# motortreiber.net
KiCad netlist of a schematic drawn in EAGLE
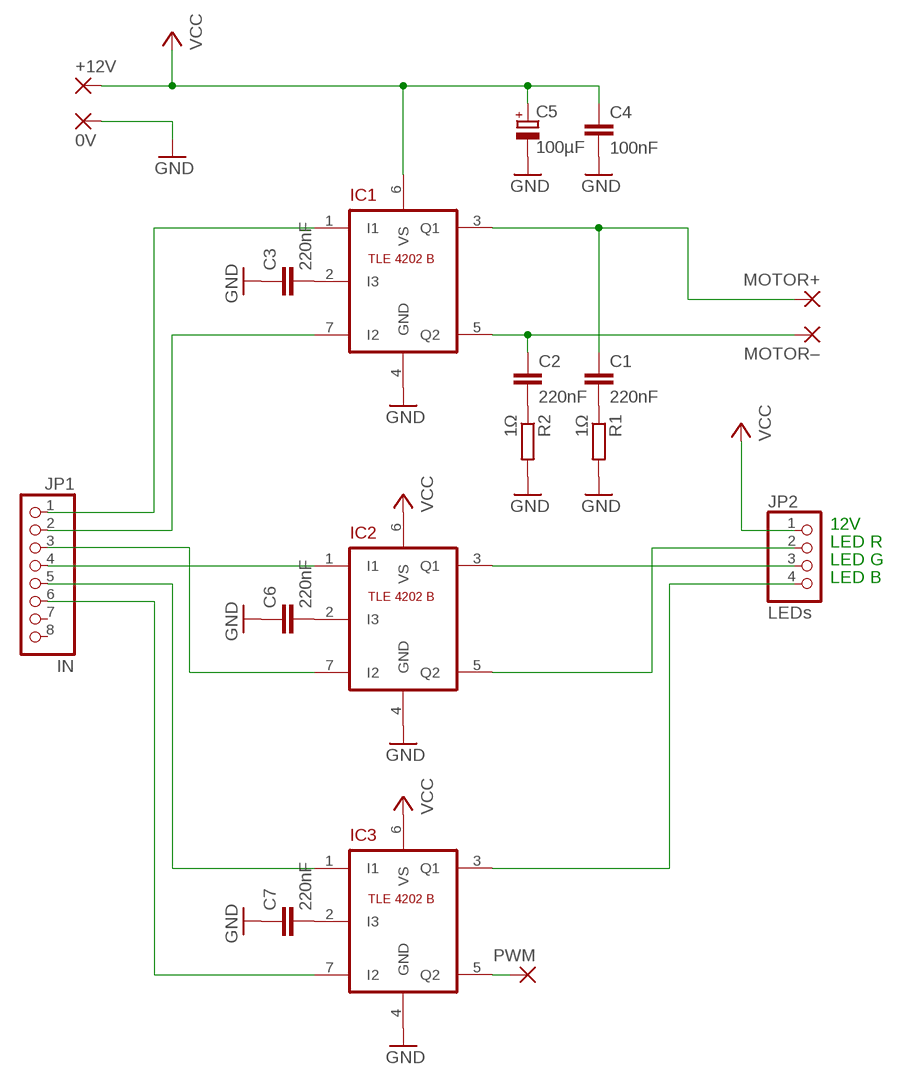
[diagram p0: schematic, sheet 1]

(export (version "E")
  (design (tool "Eeschema 10.0.6"))
  (components
    (comp (ref "+12V")
      (value "WIREPAD2,15/1,0")
      (footprint "eagle-import:2,15_1,0")
      (libsource (lib "eagle-import") (part "WIREPAD2,15/1,0"))
    )
    (comp (ref "0V")
      (value "WIREPAD2,15/1,0")
      (footprint "eagle-import:2,15_1,0")
      (libsource (lib "eagle-import") (part "WIREPAD2,15/1,0"))
    )
    (comp (ref "C1")
      (value "220nF")
      (footprint "eagle-import:C5B2.5")
      (libsource (lib "eagle-import") (part "C5/2.5"))
    )
    (comp (ref "C2")
      (value "220nF")
      (footprint "eagle-import:C5B2.5")
      (libsource (lib "eagle-import") (part "C5/2.5"))
    )
    (comp (ref "C3")
      (value "220nF")
      (footprint "eagle-import:C5B2.5")
      (libsource (lib "eagle-import") (part "C5/2.5"))
    )
    (comp (ref "C4")
      (value "100nF")
      (footprint "eagle-import:C2.5-3")
      (libsource (lib "eagle-import") (part "C2,5-3"))
    )
    (comp (ref "C5")
      (value "100µF")
      (footprint "eagle-import:E2,5-5")
      (libsource (lib "eagle-import") (part "CPOL-EUE2.5-5"))
    )
    (comp (ref "C6")
      (value "220nF")
      (footprint "eagle-import:C5B2.5")
      (libsource (lib "eagle-import") (part "C5/2.5"))
    )
    (comp (ref "C7")
      (value "220nF")
      (footprint "eagle-import:C5B2.5")
      (libsource (lib "eagle-import") (part "C5/2.5"))
    )
    (comp (ref "IC1")
      (value "TLE-4202-B-100MIL")
      (footprint "eagle-import:TO-220-7-BREADBOARD")
      (libsource (lib "eagle-import") (part "TLE-4202-B-100MIL"))
    )
    (comp (ref "IC2")
      (value "TLE-4202-B-100MIL")
      (footprint "eagle-import:TO-220-7-BREADBOARD")
      (libsource (lib "eagle-import") (part "TLE-4202-B-100MIL"))
    )
    (comp (ref "IC3")
      (value "TLE-4202-B-100MIL")
      (footprint "eagle-import:TO-220-7-BREADBOARD")
      (libsource (lib "eagle-import") (part "TLE-4202-B-100MIL"))
    )
    (comp (ref "JP1")
      (value "IN")
      (footprint "eagle-import:1X08")
      (libsource (lib "eagle-import") (part "PINHD-1X8"))
    )
    (comp (ref "JP2")
      (value "LEDs")
      (footprint "eagle-import:1X04")
      (libsource (lib "eagle-import") (part "PINHD-1X4"))
    )
    (comp (ref "MOTOR+")
      (value "WIREPAD2,15/1,0")
      (footprint "eagle-import:2,15_1,0")
      (libsource (lib "eagle-import") (part "WIREPAD2,15/1,0"))
    )
    (comp (ref "MOTOR–")
      (value "WIREPAD2,15/1,0")
      (footprint "eagle-import:2,15_1,0")
      (libsource (lib "eagle-import") (part "WIREPAD2,15/1,0"))
    )
    (comp (ref "PWM")
      (value "WIREPAD2,15/1,0")
      (footprint "eagle-import:2,15_1,0")
      (libsource (lib "eagle-import") (part "WIREPAD2,15/1,0"))
    )
    (comp (ref "R1")
      (value "1Ω")
      (footprint "eagle-import:0204_7")
      (libsource (lib "eagle-import") (part "R-EU_0204/7"))
    )
    (comp (ref "R2")
      (value "1Ω")
      (footprint "eagle-import:0204_7")
      (libsource (lib "eagle-import") (part "R-EU_0204/7"))
    )
  )
  (nets
    (net (code "1") (name "GND") (class "Default")
      (node (ref "0V") (pin "1") (pinfunction "P_1") (pintype "passive"))
      (node (ref "C3") (pin "1") (pinfunction "1_1") (pintype "passive"))
      (node (ref "C4") (pin "2") (pinfunction "2_2") (pintype "passive"))
      (node (ref "C5") (pin "-") (pinfunction "-_-") (pintype "passive"))
      (node (ref "C6") (pin "1") (pinfunction "1_1") (pintype "passive"))
      (node (ref "C7") (pin "1") (pinfunction "1_1") (pintype "passive"))
      (node (ref "IC1") (pin "4") (pinfunction "GND_4") (pintype "power_in"))
      (node (ref "IC2") (pin "4") (pinfunction "GND_4") (pintype "power_in"))
      (node (ref "IC3") (pin "4") (pinfunction "GND_4") (pintype "power_in"))
      (node (ref "R1") (pin "2") (pinfunction "2_2") (pintype "passive"))
      (node (ref "R2") (pin "2") (pinfunction "2_2") (pintype "passive"))
    )
    (net (code "2") (name "Net-(C1-Pad2)") (class "Default")
      (node (ref "C1") (pin "2") (pinfunction "2_2") (pintype "passive"))
      (node (ref "R1") (pin "1") (pinfunction "1_1") (pintype "passive"))
    )
    (net (code "3") (name "Net-(C2-Pad2)") (class "Default")
      (node (ref "C2") (pin "2") (pinfunction "2_2") (pintype "passive"))
      (node (ref "R2") (pin "1") (pinfunction "1_1") (pintype "passive"))
    )
    (net (code "4") (name "Net-(IC1-I1)") (class "Default")
      (node (ref "IC1") (pin "1") (pinfunction "I1_1") (pintype "input"))
      (node (ref "JP1") (pin "1") (pinfunction "1_1") (pintype "passive"))
    )
    (net (code "5") (name "Net-(IC1-I2)") (class "Default")
      (node (ref "IC1") (pin "7") (pinfunction "I2_7") (pintype "input"))
      (node (ref "JP1") (pin "2") (pinfunction "2_2") (pintype "passive"))
    )
    (net (code "6") (name "Net-(IC1-I3)") (class "Default")
      (node (ref "C3") (pin "2") (pinfunction "2_2") (pintype "passive"))
      (node (ref "IC1") (pin "2") (pinfunction "I3_2") (pintype "input"))
    )
    (net (code "7") (name "Net-(IC1-Q1)") (class "Default")
      (node (ref "C1") (pin "1") (pinfunction "1_1") (pintype "passive"))
      (node (ref "IC1") (pin "3") (pinfunction "Q1_3") (pintype "output"))
      (node (ref "MOTOR+") (pin "1") (pinfunction "P_1") (pintype "passive"))
    )
    (net (code "8") (name "Net-(IC1-Q2)") (class "Default")
      (node (ref "C2") (pin "1") (pinfunction "1_1") (pintype "passive"))
      (node (ref "IC1") (pin "5") (pinfunction "Q2_5") (pintype "output"))
      (node (ref "MOTOR–") (pin "1") (pinfunction "P_1") (pintype "passive"))
    )
    (net (code "9") (name "Net-(IC2-I1)") (class "Default")
      (node (ref "IC2") (pin "1") (pinfunction "I1_1") (pintype "input"))
      (node (ref "JP1") (pin "4") (pinfunction "4_4") (pintype "passive"))
    )
    (net (code "10") (name "Net-(IC2-I2)") (class "Default")
      (node (ref "IC2") (pin "7") (pinfunction "I2_7") (pintype "input"))
      (node (ref "JP1") (pin "3") (pinfunction "3_3") (pintype "passive"))
    )
    (net (code "11") (name "Net-(IC2-I3)") (class "Default")
      (node (ref "C6") (pin "2") (pinfunction "2_2") (pintype "passive"))
      (node (ref "IC2") (pin "2") (pinfunction "I3_2") (pintype "input"))
    )
    (net (code "12") (name "Net-(IC2-Q1)") (class "Default")
      (node (ref "IC2") (pin "3") (pinfunction "Q1_3") (pintype "output"))
      (node (ref "JP2") (pin "3") (pinfunction "3_3") (pintype "passive"))
    )
    (net (code "13") (name "Net-(IC2-Q2)") (class "Default")
      (node (ref "IC2") (pin "5") (pinfunction "Q2_5") (pintype "output"))
      (node (ref "JP2") (pin "2") (pinfunction "2_2") (pintype "passive"))
    )
    (net (code "14") (name "Net-(IC3-I1)") (class "Default")
      (node (ref "IC3") (pin "1") (pinfunction "I1_1") (pintype "input"))
      (node (ref "JP1") (pin "5") (pinfunction "5_5") (pintype "passive"))
    )
    (net (code "15") (name "Net-(IC3-I2)") (class "Default")
      (node (ref "IC3") (pin "7") (pinfunction "I2_7") (pintype "input"))
      (node (ref "JP1") (pin "6") (pinfunction "6_6") (pintype "passive"))
    )
    (net (code "16") (name "Net-(IC3-I3)") (class "Default")
      (node (ref "C7") (pin "2") (pinfunction "2_2") (pintype "passive"))
      (node (ref "IC3") (pin "2") (pinfunction "I3_2") (pintype "input"))
    )
    (net (code "17") (name "Net-(IC3-Q1)") (class "Default")
      (node (ref "IC3") (pin "3") (pinfunction "Q1_3") (pintype "output"))
      (node (ref "JP2") (pin "4") (pinfunction "4_4") (pintype "passive"))
    )
    (net (code "18") (name "Net-(IC3-Q2)") (class "Default")
      (node (ref "IC3") (pin "5") (pinfunction "Q2_5") (pintype "output"))
      (node (ref "PWM") (pin "1") (pinfunction "P_1") (pintype "passive"))
    )
    (net (code "19") (name "VCC") (class "Default")
      (node (ref "+12V") (pin "1") (pinfunction "P_1") (pintype "passive"))
      (node (ref "C4") (pin "1") (pinfunction "1_1") (pintype "passive"))
      (node (ref "C5") (pin "+") (pinfunction "+_+") (pintype "passive"))
      (node (ref "IC1") (pin "6") (pinfunction "VS_6") (pintype "power_in"))
      (node (ref "IC2") (pin "6") (pinfunction "VS_6") (pintype "power_in"))
      (node (ref "IC3") (pin "6") (pinfunction "VS_6") (pintype "power_in"))
      (node (ref "JP2") (pin "1") (pinfunction "1_1") (pintype "passive"))
    )
    (net (code "20") (name "unconnected-(JP1-Pad7)") (class "Default")
      (node (ref "JP1") (pin "7") (pinfunction "7_7") (pintype "passive"))
    )
    (net (code "21") (name "unconnected-(JP1-Pad8)") (class "Default")
      (node (ref "JP1") (pin "8") (pinfunction "8_8") (pintype "passive"))
    )
  )
)
